# Sheet1.net
KiCad netlist of a schematic drawn in Altium Designer
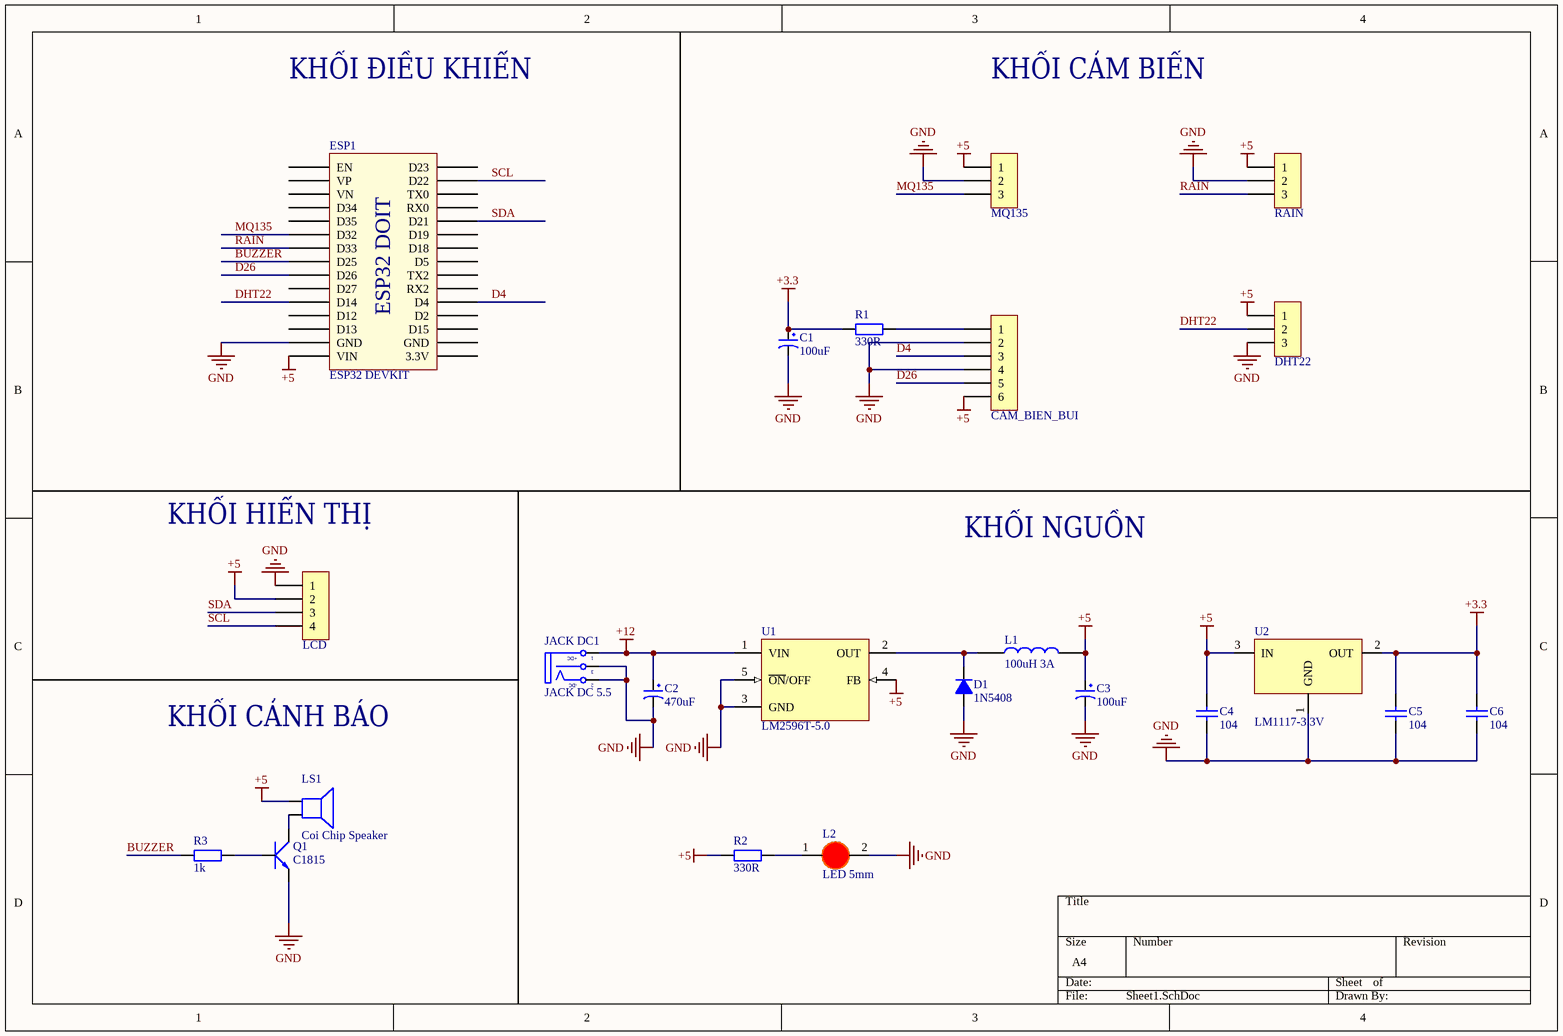
[diagram p0: Sheet1.SchDoc]

(export (version "E")
  (design (tool "Eeschema 10.0.6"))
  (components
    (comp (ref "C1")
      (value "100uF")
      (footprint "tu hoa 8mm")
      (description "Cắm")
      (libsource (lib "Altium_Lib_by_KhueNguyenCreator") (part "Tu Hoa 100uF 50V 8x11"))
    )
    (comp (ref "C2")
      (value "470uF")
      (footprint "tu hoa 8mm")
      (description "Cắm")
      (libsource (lib "Altium_Lib_by_KhueNguyenCreator") (part "Tu Hoa 470uF 25V 8x13"))
    )
    (comp (ref "C3")
      (value "100uF")
      (footprint "tu hoa 8mm")
      (description "Cắm")
      (libsource (lib "Altium_Lib_by_KhueNguyenCreator") (part "Tu Hoa 100uF 50V 8x11"))
    )
    (comp (ref "C4")
      (value "104")
      (footprint "tu gom")
      (description "Cắm")
      (libsource (lib "Altium_Lib_by_KhueNguyenCreator") (part "Tu gom 104 50V"))
    )
    (comp (ref "C5")
      (value "104")
      (footprint "tu gom")
      (description "Cắm")
      (libsource (lib "Altium_Lib_by_KhueNguyenCreator") (part "Tu gom 104 50V"))
    )
    (comp (ref "C6")
      (value "104")
      (footprint "tu gom")
      (description "Cắm")
      (libsource (lib "Altium_Lib_by_KhueNguyenCreator") (part "Tu gom 104 50V"))
    )
    (comp (ref "D1")
      (value "1N5408")
      (footprint "D5A")
      (description "Diode 5A")
      (libsource (lib "Cty1") (part "D5A"))
    )
    (comp (ref "ESP1")
      (value "ESP32 DEVKIT")
      (footprint "ESP32 WROOM 32 KIT")
      (libsource (lib "Altium_Lib_by_KhueNguyenCreator") (part "ESP32 WROOM 32 KIT"))
    )
    (comp (ref "H1")
      (value "MQ135")
      (footprint "XH2.54M-3")
      (description "Cắm")
      (libsource (lib "Altium_Lib_by_KhueNguyenCreator") (part "Header 3P 2.54 Duc Thang"))
    )
    (comp (ref "H2")
      (value "RAIN")
      (footprint "XH2.54M-3")
      (description "Cắm")
      (libsource (lib "Altium_Lib_by_KhueNguyenCreator") (part "Header 3P 2.54 Duc Thang"))
    )
    (comp (ref "H3")
      (value "DHT22")
      (footprint "XH2.54M-3")
      (description "Cắm")
      (libsource (lib "Altium_Lib_by_KhueNguyenCreator") (part "Header 3P 2.54 Duc Thang"))
    )
    (comp (ref "H4")
      (value "CAM_BIEN_BUI")
      (footprint "XH2.54M-6")
      (description "Cắm")
      (libsource (lib "Altium_Lib_by_KhueNguyenCreator") (part "Header 6P 2.54 Duc Thang"))
    )
    (comp (ref "H5")
      (value "LCD")
      (footprint "XH2.54M-4")
      (description "Cắm")
      (libsource (lib "Altium_Lib_by_KhueNguyenCreator") (part "Header 4P 2.54 Duc Thang"))
    )
    (comp (ref "JACK DC1")
      (value "JACK DC 5.5")
      (footprint "JACK DC 5.5")
      (libsource (lib "Altium_Lib_by_KhueNguyenCreator") (part "JACK DC 5.5"))
    )
    (comp (ref "L1")
      (value "100uH 3A")
      (footprint "CUON CAM 100uH3A")
      (description "Dán")
      (libsource (lib "Altium_Lib_by_KhueNguyenCreator") (part "CUON CAM 100uH DIP"))
    )
    (comp (ref "L2")
      (value "LED 5mm")
      (footprint "LED-5MM-RED")
      (description "Cắm")
      (libsource (lib "Altium_Lib_by_KhueNguyenCreator") (part "LED 5mm Do"))
    )
    (comp (ref "LS1")
      (value "Coi Chip Speaker")
      (footprint "Coi Chip Speacker")
      (description "Còi chip")
      (libsource (lib "Altium_Lib_by_KhueNguyenCreator") (part "Coi Chip Speaker"))
    )
    (comp (ref "Q1")
      (value "C1815")
      (footprint "TO92")
      (description "NPN transistor")
      (libsource (lib "Altium_Lib_by_KhueNguyenCreator") (part "Trans C1815 DIP"))
    )
    (comp (ref "R1")
      (value "330R")
      (footprint "tro vach 1/4w")
      (description "Cắm")
      (libsource (lib "Altium_Lib_by_KhueNguyenCreator") (part "Tro Vach 1/4W 5% 330R"))
    )
    (comp (ref "R2")
      (value "330R")
      (footprint "tro vach 1/4w")
      (description "Cắm")
      (libsource (lib "Altium_Lib_by_KhueNguyenCreator") (part "Tro Vach 1/4W 5% 330R"))
    )
    (comp (ref "R3")
      (value "1k")
      (footprint "tro vach 1/4w")
      (description "Cắm")
      (libsource (lib "Altium_Lib_by_KhueNguyenCreator") (part "Tro Vach 1/4W 5% 1k"))
    )
    (comp (ref "U1")
      (value "LM2596T-5.0")
      (footprint "LM2576t")
      (description "SIMPLE SWITCHER; 3A Step-Down Voltage Regulator")
      (fields
        (field (name "PARTNUMBER") "LM2576T-5.0")
        (field (name "MANUFACTURER") "National Semiconductor")
        (field (name "PUBLISHER") "Altium Limited")
      )
      (libsource (lib "Cty1") (part "LM2576T-5.0"))
    )
    (comp (ref "U2")
      (value "LM1117-3.3V")
      (footprint "SOT223-4N")
      (description "800mA Low-Dropout Linear Regulator")
      (fields (field (name "CREATOR") "Nguyen Ba Bien"))
      (libsource (lib "Cty1") (part "LM1117"))
    )
  )
  (nets
    (net (code "1") (name "+3.3") (class "Default")
      (node (ref "C1") (pin "1") (pinfunction "1_1") (pintype "passive"))
      (node (ref "C5") (pin "1") (pinfunction "1_1") (pintype "passive"))
      (node (ref "C6") (pin "1") (pinfunction "1_1") (pintype "passive"))
      (node (ref "R1") (pin "1") (pinfunction "1_1") (pintype "passive"))
      (node (ref "U2") (pin "2") (pinfunction "OUT_2") (pintype "passive"))
    )
    (net (code "2") (name "+5") (class "Default")
      (node (ref "C3") (pin "1") (pinfunction "1_1") (pintype "passive"))
      (node (ref "C4") (pin "1") (pinfunction "1_1") (pintype "passive"))
      (node (ref "ESP1") (pin "15") (pinfunction "VIN_15") (pintype "passive"))
      (node (ref "H1") (pin "1") (pinfunction "1_1") (pintype "passive"))
      (node (ref "H2") (pin "1") (pinfunction "1_1") (pintype "passive"))
      (node (ref "H3") (pin "1") (pinfunction "1_1") (pintype "passive"))
      (node (ref "H4") (pin "6") (pinfunction "6_6") (pintype "passive"))
      (node (ref "H5") (pin "2") (pinfunction "2_2") (pintype "passive"))
      (node (ref "L1") (pin "2") (pinfunction "2_2") (pintype "passive"))
      (node (ref "LS1") (pin "1") (pinfunction "1_1") (pintype "passive"))
      (node (ref "R2") (pin "1") (pinfunction "1_1") (pintype "passive"))
      (node (ref "U1") (pin "4") (pinfunction "FB_4") (pintype "input"))
      (node (ref "U2") (pin "3") (pinfunction "IN_3") (pintype "passive"))
    )
    (net (code "3") (name "+12") (class "Default")
      (node (ref "C2") (pin "1") (pinfunction "1_1") (pintype "passive"))
      (node (ref "JACK DC1") (pin "1") (pinfunction "T_1") (pintype "passive"))
      (node (ref "U1") (pin "1") (pinfunction "VIN_1") (pintype "power_in"))
    )
    (net (code "4") (name "/BUZZER") (class "Default")
      (node (ref "ESP1") (pin "8") (pinfunction "D25_8") (pintype "passive"))
      (node (ref "R3") (pin "1") (pinfunction "1_1") (pintype "passive"))
    )
    (net (code "5") (name "/D4") (class "Default")
      (node (ref "ESP1") (pin "20") (pinfunction "D4_20") (pintype "passive"))
      (node (ref "H4") (pin "3") (pinfunction "3_3") (pintype "passive"))
    )
    (net (code "6") (name "/D26") (class "Default")
      (node (ref "ESP1") (pin "9") (pinfunction "D26_9") (pintype "passive"))
      (node (ref "H4") (pin "5") (pinfunction "5_5") (pintype "passive"))
    )
    (net (code "7") (name "/DHT22") (class "Default")
      (node (ref "ESP1") (pin "11") (pinfunction "D14_11") (pintype "passive"))
      (node (ref "H3") (pin "2") (pinfunction "2_2") (pintype "passive"))
    )
    (net (code "8") (name "/MQ135") (class "Default")
      (node (ref "ESP1") (pin "6") (pinfunction "D32_6") (pintype "passive"))
      (node (ref "H1") (pin "3") (pinfunction "3_3") (pintype "passive"))
    )
    (net (code "9") (name "/RAIN") (class "Default")
      (node (ref "ESP1") (pin "7") (pinfunction "D33_7") (pintype "passive"))
      (node (ref "H2") (pin "3") (pinfunction "3_3") (pintype "passive"))
    )
    (net (code "10") (name "/SCL") (class "Default")
      (node (ref "ESP1") (pin "29") (pinfunction "D22_29") (pintype "passive"))
      (node (ref "H5") (pin "4") (pinfunction "4_4") (pintype "passive"))
    )
    (net (code "11") (name "/SDA") (class "Default")
      (node (ref "ESP1") (pin "26") (pinfunction "D21_26") (pintype "passive"))
      (node (ref "H5") (pin "3") (pinfunction "3_3") (pintype "passive"))
    )
    (net (code "12") (name "GND") (class "Default")
      (node (ref "C1") (pin "2") (pinfunction "2_2") (pintype "passive"))
      (node (ref "C2") (pin "2") (pinfunction "2_2") (pintype "passive"))
      (node (ref "C3") (pin "2") (pinfunction "2_2") (pintype "passive"))
      (node (ref "C4") (pin "2") (pinfunction "2_2") (pintype "passive"))
      (node (ref "C5") (pin "2") (pinfunction "2_2") (pintype "passive"))
      (node (ref "C6") (pin "2") (pinfunction "2_2") (pintype "passive"))
      (node (ref "D1") (pin "1") (pinfunction "A_1") (pintype "passive"))
      (node (ref "ESP1") (pin "14") (pinfunction "GND_14") (pintype "passive"))
      (node (ref "H1") (pin "2") (pinfunction "2_2") (pintype "passive"))
      (node (ref "H2") (pin "2") (pinfunction "2_2") (pintype "passive"))
      (node (ref "H3") (pin "3") (pinfunction "3_3") (pintype "passive"))
      (node (ref "H4") (pin "2") (pinfunction "2_2") (pintype "passive"))
      (node (ref "H4") (pin "4") (pinfunction "4_4") (pintype "passive"))
      (node (ref "H5") (pin "1") (pinfunction "1_1") (pintype "passive"))
      (node (ref "JACK DC1") (pin "2") (pinfunction "TN_2") (pintype "passive"))
      (node (ref "JACK DC1") (pin "3") (pinfunction "S_3") (pintype "power_in"))
      (node (ref "L2") (pin "2") (pinfunction "K_2") (pintype "passive"))
      (node (ref "Q1") (pin "1") (pinfunction "E_1") (pintype "passive"))
      (node (ref "U1") (pin "3") (pinfunction "GND_3") (pintype "power_in"))
      (node (ref "U1") (pin "5") (pinfunction "~{ON}/OFF_5") (pintype "input"))
      (node (ref "U2") (pin "1") (pinfunction "GND_1") (pintype "passive"))
    )
    (net (code "13") (name "Net-(D1-K)") (class "Default")
      (node (ref "D1") (pin "2") (pinfunction "K_2") (pintype "passive"))
      (node (ref "L1") (pin "1") (pinfunction "1_1") (pintype "passive"))
      (node (ref "U1") (pin "2") (pinfunction "OUT_2") (pintype "power_in"))
    )
    (net (code "14") (name "Net-(H4-Pad1)") (class "Default")
      (node (ref "H4") (pin "1") (pinfunction "1_1") (pintype "passive"))
      (node (ref "R1") (pin "2") (pinfunction "2_2") (pintype "passive"))
    )
    (net (code "15") (name "Net-(L2-A)") (class "Default")
      (node (ref "L2") (pin "1") (pinfunction "A_1") (pintype "passive"))
      (node (ref "R2") (pin "2") (pinfunction "2_2") (pintype "passive"))
    )
    (net (code "16") (name "Net-(Q1-B)") (class "Default")
      (node (ref "Q1") (pin "3") (pinfunction "B_3") (pintype "passive"))
      (node (ref "R3") (pin "2") (pinfunction "2_2") (pintype "passive"))
    )
    (net (code "17") (name "Net-(Q1-C)") (class "Default")
      (node (ref "LS1") (pin "2") (pinfunction "2_2") (pintype "passive"))
      (node (ref "Q1") (pin "2") (pinfunction "C_2") (pintype "passive"))
    )
    (net (code "18") (name "unconnected-(ESP1-3.3V-Pad16)") (class "Default")
      (node (ref "ESP1") (pin "16") (pinfunction "3.3V_16") (pintype "passive"))
    )
    (net (code "19") (name "unconnected-(ESP1-D2-Pad19)") (class "Default")
      (node (ref "ESP1") (pin "19") (pinfunction "D2_19") (pintype "passive"))
    )
    (net (code "20") (name "unconnected-(ESP1-D5-Pad23)") (class "Default")
      (node (ref "ESP1") (pin "23") (pinfunction "D5_23") (pintype "passive"))
    )
    (net (code "21") (name "unconnected-(ESP1-D12-Pad12)") (class "Default")
      (node (ref "ESP1") (pin "12") (pinfunction "D12_12") (pintype "passive"))
    )
    (net (code "22") (name "unconnected-(ESP1-D13-Pad13)") (class "Default")
      (node (ref "ESP1") (pin "13") (pinfunction "D13_13") (pintype "passive"))
    )
    (net (code "23") (name "unconnected-(ESP1-D15-Pad18)") (class "Default")
      (node (ref "ESP1") (pin "18") (pinfunction "D15_18") (pintype "passive"))
    )
    (net (code "24") (name "unconnected-(ESP1-D18-Pad24)") (class "Default")
      (node (ref "ESP1") (pin "24") (pinfunction "D18_24") (pintype "passive"))
    )
    (net (code "25") (name "unconnected-(ESP1-D19-Pad25)") (class "Default")
      (node (ref "ESP1") (pin "25") (pinfunction "D19_25") (pintype "passive"))
    )
    (net (code "26") (name "unconnected-(ESP1-D23-Pad30)") (class "Default")
      (node (ref "ESP1") (pin "30") (pinfunction "D23_30") (pintype "passive"))
    )
    (net (code "27") (name "unconnected-(ESP1-D27-Pad10)") (class "Default")
      (node (ref "ESP1") (pin "10") (pinfunction "D27_10") (pintype "passive"))
    )
    (net (code "28") (name "unconnected-(ESP1-D34-Pad4)") (class "Default")
      (node (ref "ESP1") (pin "4") (pinfunction "D34_4") (pintype "passive"))
    )
    (net (code "29") (name "unconnected-(ESP1-D35-Pad5)") (class "Default")
      (node (ref "ESP1") (pin "5") (pinfunction "D35_5") (pintype "passive"))
    )
    (net (code "30") (name "unconnected-(ESP1-EN-Pad1)") (class "Default")
      (node (ref "ESP1") (pin "1") (pinfunction "EN_1") (pintype "passive"))
    )
    (net (code "31") (name "unconnected-(ESP1-GND-Pad17)") (class "Default")
      (node (ref "ESP1") (pin "17") (pinfunction "GND_17") (pintype "passive"))
    )
    (net (code "32") (name "unconnected-(ESP1-RX0-Pad27)") (class "Default")
      (node (ref "ESP1") (pin "27") (pinfunction "RX0_27") (pintype "passive"))
    )
    (net (code "33") (name "unconnected-(ESP1-RX2-Pad21)") (class "Default")
      (node (ref "ESP1") (pin "21") (pinfunction "RX2_21") (pintype "passive"))
    )
    (net (code "34") (name "unconnected-(ESP1-TX0-Pad28)") (class "Default")
      (node (ref "ESP1") (pin "28") (pinfunction "TX0_28") (pintype "passive"))
    )
    (net (code "35") (name "unconnected-(ESP1-TX2-Pad22)") (class "Default")
      (node (ref "ESP1") (pin "22") (pinfunction "TX2_22") (pintype "passive"))
    )
    (net (code "36") (name "unconnected-(ESP1-VN-Pad3)") (class "Default")
      (node (ref "ESP1") (pin "3") (pinfunction "VN_3") (pintype "passive"))
    )
    (net (code "37") (name "unconnected-(ESP1-VP-Pad2)") (class "Default")
      (node (ref "ESP1") (pin "2") (pinfunction "VP_2") (pintype "passive"))
    )
  )
)
